# Current_Shunts.net
KiCad netlist of a schematic drawn in Altium Designer
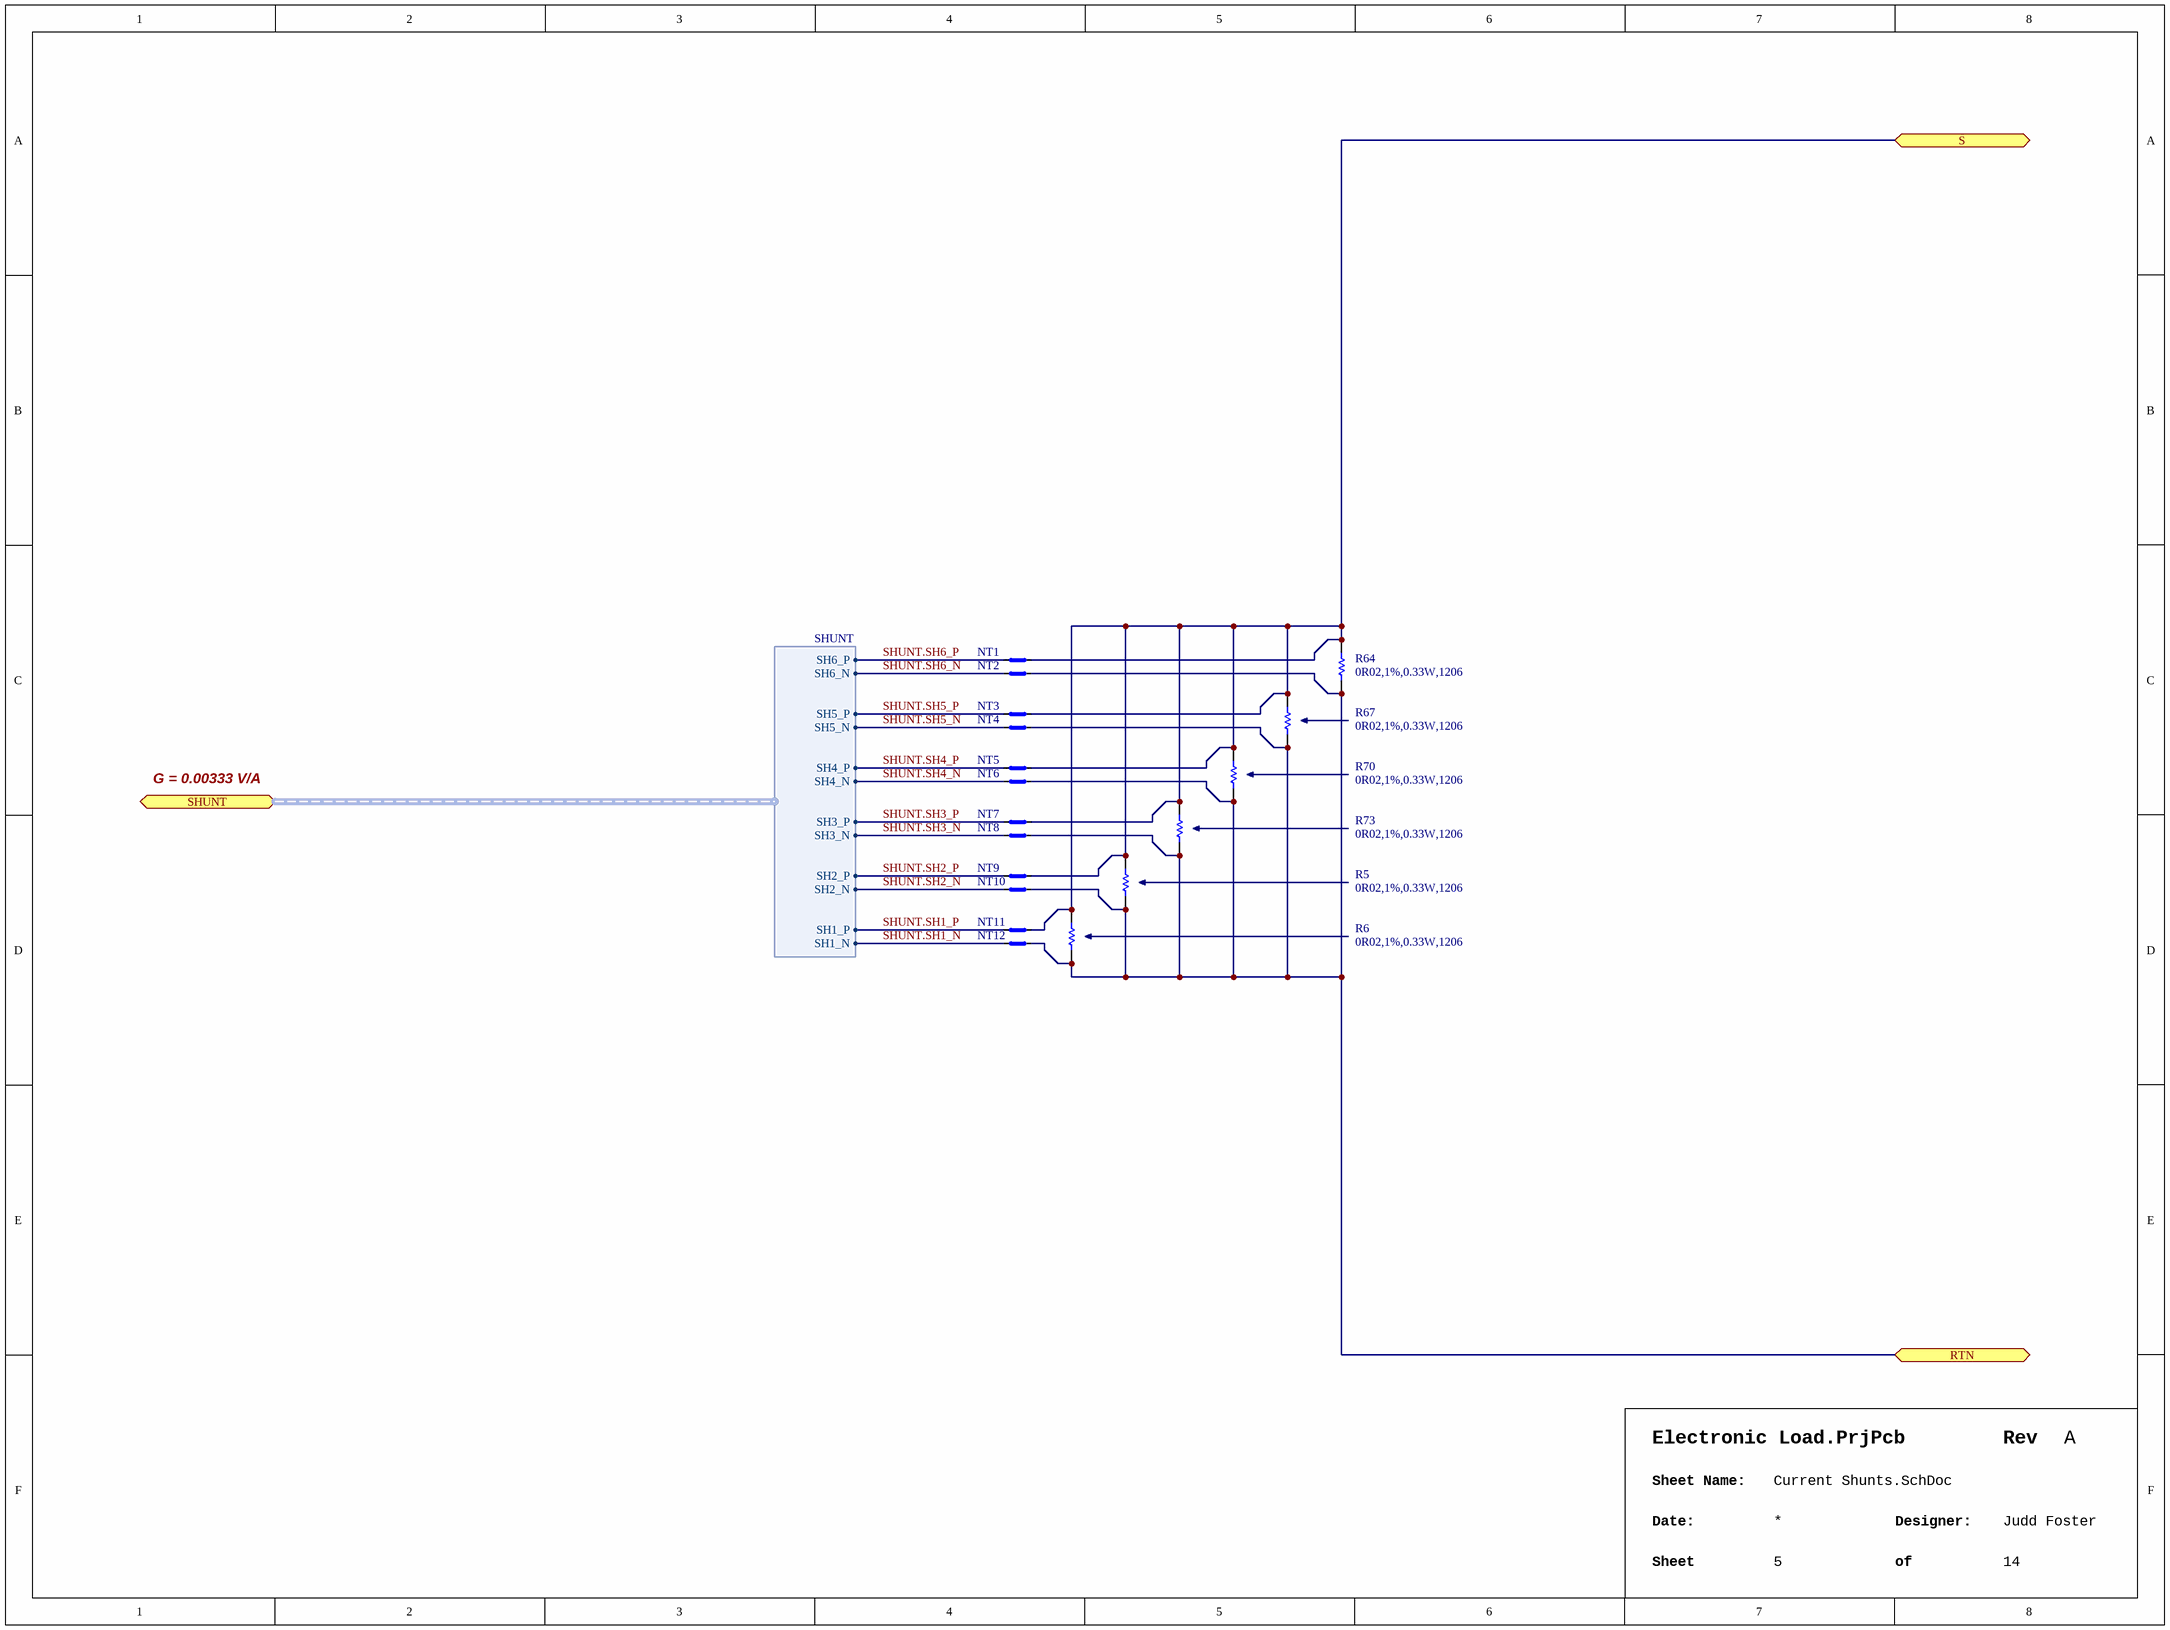
[diagram p0: Current Shunts.SchDoc]

(export (version "E")
  (design (tool "Eeschema 10.0.6"))
  (components
    (comp (ref "NT1")
      (value "NETTIE")
      (footprint "NETTIE_150X300UM")
      (description "Net Tie")
      (fields (field (name "CREATEDBY") "Judd Foster"))
      (libsource (lib "Component Library") (part "NETTIE"))
    )
    (comp (ref "NT2")
      (value "NETTIE")
      (footprint "NETTIE_150X300UM")
      (description "Net Tie")
      (fields (field (name "CREATEDBY") "Judd Foster"))
      (libsource (lib "Component Library") (part "NETTIE"))
    )
    (comp (ref "NT3")
      (value "NETTIE")
      (footprint "NETTIE_150X300UM")
      (description "Net Tie")
      (fields (field (name "CREATEDBY") "Judd Foster"))
      (libsource (lib "Component Library") (part "NETTIE"))
    )
    (comp (ref "NT4")
      (value "NETTIE")
      (footprint "NETTIE_150X300UM")
      (description "Net Tie")
      (fields (field (name "CREATEDBY") "Judd Foster"))
      (libsource (lib "Component Library") (part "NETTIE"))
    )
    (comp (ref "NT5")
      (value "NETTIE")
      (footprint "NETTIE_150X300UM")
      (description "Net Tie")
      (fields (field (name "CREATEDBY") "Judd Foster"))
      (libsource (lib "Component Library") (part "NETTIE"))
    )
    (comp (ref "NT6")
      (value "NETTIE")
      (footprint "NETTIE_150X300UM")
      (description "Net Tie")
      (fields (field (name "CREATEDBY") "Judd Foster"))
      (libsource (lib "Component Library") (part "NETTIE"))
    )
    (comp (ref "NT7")
      (value "NETTIE")
      (footprint "NETTIE_150X300UM")
      (description "Net Tie")
      (fields (field (name "CREATEDBY") "Judd Foster"))
      (libsource (lib "Component Library") (part "NETTIE"))
    )
    (comp (ref "NT8")
      (value "NETTIE")
      (footprint "NETTIE_150X300UM")
      (description "Net Tie")
      (fields (field (name "CREATEDBY") "Judd Foster"))
      (libsource (lib "Component Library") (part "NETTIE"))
    )
    (comp (ref "NT9")
      (value "NETTIE")
      (footprint "NETTIE_150X300UM")
      (description "Net Tie")
      (fields (field (name "CREATEDBY") "Judd Foster"))
      (libsource (lib "Component Library") (part "NETTIE"))
    )
    (comp (ref "NT10")
      (value "NETTIE")
      (footprint "NETTIE_150X300UM")
      (description "Net Tie")
      (fields (field (name "CREATEDBY") "Judd Foster"))
      (libsource (lib "Component Library") (part "NETTIE"))
    )
    (comp (ref "NT11")
      (value "NETTIE")
      (footprint "NETTIE_150X300UM")
      (description "Net Tie")
      (fields (field (name "CREATEDBY") "Judd Foster"))
      (libsource (lib "Component Library") (part "NETTIE"))
    )
    (comp (ref "NT12")
      (value "NETTIE")
      (footprint "NETTIE_150X300UM")
      (description "Net Tie")
      (fields (field (name "CREATEDBY") "Judd Foster"))
      (libsource (lib "Component Library") (part "NETTIE"))
    )
    (comp (ref "R5")
      (value "0R02,1%,0.33W,1206")
      (footprint "RESC3216X06N")
      (description "333mW 20mÎ© 200V Â±1000ppm/â„ƒ Thick Film Resistor Â±1% 1206 Chip Resistor - Surface Mount ROHS")
      (fields
        (field (name "MANUFACTURER 1 PART NUMBER") "1206W3F200MT5E")
        (field (name "VENDOR 1 PART NUMBER") "C2765435")
        (field (name "CREATEDBY") "Judd Foster")
      )
      (libsource (lib "Component Library") (part "RES"))
    )
    (comp (ref "R6")
      (value "0R02,1%,0.33W,1206")
      (footprint "RESC3216X06N")
      (description "333mW 20mÎ© 200V Â±1000ppm/â„ƒ Thick Film Resistor Â±1% 1206 Chip Resistor - Surface Mount ROHS")
      (fields
        (field (name "MANUFACTURER 1 PART NUMBER") "1206W3F200MT5E")
        (field (name "VENDOR 1 PART NUMBER") "C2765435")
        (field (name "CREATEDBY") "Judd Foster")
      )
      (libsource (lib "Component Library") (part "RES"))
    )
    (comp (ref "R64")
      (value "0R02,1%,0.33W,1206")
      (footprint "RESC3216X06N")
      (description "333mW 20mÎ© 200V Â±1000ppm/â„ƒ Thick Film Resistor Â±1% 1206 Chip Resistor - Surface Mount ROHS")
      (fields
        (field (name "MANUFACTURER 1 PART NUMBER") "1206W3F200MT5E")
        (field (name "VENDOR 1 PART NUMBER") "C2765435")
        (field (name "CREATEDBY") "Judd Foster")
      )
      (libsource (lib "Component Library") (part "RES"))
    )
    (comp (ref "R67")
      (value "0R02,1%,0.33W,1206")
      (footprint "RESC3216X06N")
      (description "333mW 20mÎ© 200V Â±1000ppm/â„ƒ Thick Film Resistor Â±1% 1206 Chip Resistor - Surface Mount ROHS")
      (fields
        (field (name "MANUFACTURER 1 PART NUMBER") "1206W3F200MT5E")
        (field (name "VENDOR 1 PART NUMBER") "C2765435")
        (field (name "CREATEDBY") "Judd Foster")
      )
      (libsource (lib "Component Library") (part "RES"))
    )
    (comp (ref "R70")
      (value "0R02,1%,0.33W,1206")
      (footprint "RESC3216X06N")
      (description "333mW 20mÎ© 200V Â±1000ppm/â„ƒ Thick Film Resistor Â±1% 1206 Chip Resistor - Surface Mount ROHS")
      (fields
        (field (name "MANUFACTURER 1 PART NUMBER") "1206W3F200MT5E")
        (field (name "VENDOR 1 PART NUMBER") "C2765435")
        (field (name "CREATEDBY") "Judd Foster")
      )
      (libsource (lib "Component Library") (part "RES"))
    )
    (comp (ref "R73")
      (value "0R02,1%,0.33W,1206")
      (footprint "RESC3216X06N")
      (description "333mW 20mÎ© 200V Â±1000ppm/â„ƒ Thick Film Resistor Â±1% 1206 Chip Resistor - Surface Mount ROHS")
      (fields
        (field (name "MANUFACTURER 1 PART NUMBER") "1206W3F200MT5E")
        (field (name "VENDOR 1 PART NUMBER") "C2765435")
        (field (name "CREATEDBY") "Judd Foster")
      )
      (libsource (lib "Component Library") (part "RES"))
    )
  )
  (nets
    (net (code "2") (name "/RTN") (class "Default")
      (node (ref "NT10") (pin "2") (pinfunction "2_2") (pintype "passive"))
      (node (ref "NT12") (pin "2") (pinfunction "2_2") (pintype "passive"))
      (node (ref "NT2") (pin "2") (pinfunction "2_2") (pintype "passive"))
      (node (ref "NT4") (pin "2") (pinfunction "2_2") (pintype "passive"))
      (node (ref "NT6") (pin "2") (pinfunction "2_2") (pintype "passive"))
      (node (ref "NT8") (pin "2") (pinfunction "2_2") (pintype "passive"))
      (node (ref "R5") (pin "1") (pinfunction "1_1") (pintype "passive"))
      (node (ref "R6") (pin "1") (pinfunction "1_1") (pintype "passive"))
      (node (ref "R64") (pin "1") (pinfunction "1_1") (pintype "passive"))
      (node (ref "R67") (pin "1") (pinfunction "1_1") (pintype "passive"))
      (node (ref "R70") (pin "1") (pinfunction "1_1") (pintype "passive"))
      (node (ref "R73") (pin "1") (pinfunction "1_1") (pintype "passive"))
    )
    (net (code "3") (name "/S") (class "Default")
      (node (ref "NT1") (pin "2") (pinfunction "2_2") (pintype "passive"))
      (node (ref "NT11") (pin "2") (pinfunction "2_2") (pintype "passive"))
      (node (ref "NT3") (pin "2") (pinfunction "2_2") (pintype "passive"))
      (node (ref "NT5") (pin "2") (pinfunction "2_2") (pintype "passive"))
      (node (ref "NT7") (pin "2") (pinfunction "2_2") (pintype "passive"))
      (node (ref "NT9") (pin "2") (pinfunction "2_2") (pintype "passive"))
      (node (ref "R5") (pin "2") (pinfunction "2_2") (pintype "passive"))
      (node (ref "R6") (pin "2") (pinfunction "2_2") (pintype "passive"))
      (node (ref "R64") (pin "2") (pinfunction "2_2") (pintype "passive"))
      (node (ref "R67") (pin "2") (pinfunction "2_2") (pintype "passive"))
      (node (ref "R70") (pin "2") (pinfunction "2_2") (pintype "passive"))
      (node (ref "R73") (pin "2") (pinfunction "2_2") (pintype "passive"))
    )
    (net (code "4") (name "/SHUNT.SH1_N") (class "Default")
      (node (ref "NT12") (pin "1") (pinfunction "1_1") (pintype "passive"))
    )
    (net (code "5") (name "/SHUNT.SH1_P") (class "Default")
      (node (ref "NT11") (pin "1") (pinfunction "1_1") (pintype "passive"))
    )
    (net (code "6") (name "/SHUNT.SH2_N") (class "Default")
      (node (ref "NT10") (pin "1") (pinfunction "1_1") (pintype "passive"))
    )
    (net (code "7") (name "/SHUNT.SH2_P") (class "Default")
      (node (ref "NT9") (pin "1") (pinfunction "1_1") (pintype "passive"))
    )
    (net (code "8") (name "/SHUNT.SH3_N") (class "Default")
      (node (ref "NT8") (pin "1") (pinfunction "1_1") (pintype "passive"))
    )
    (net (code "9") (name "/SHUNT.SH3_P") (class "Default")
      (node (ref "NT7") (pin "1") (pinfunction "1_1") (pintype "passive"))
    )
    (net (code "10") (name "/SHUNT.SH4_N") (class "Default")
      (node (ref "NT6") (pin "1") (pinfunction "1_1") (pintype "passive"))
    )
    (net (code "11") (name "/SHUNT.SH4_P") (class "Default")
      (node (ref "NT5") (pin "1") (pinfunction "1_1") (pintype "passive"))
    )
    (net (code "12") (name "/SHUNT.SH5_N") (class "Default")
      (node (ref "NT4") (pin "1") (pinfunction "1_1") (pintype "passive"))
    )
    (net (code "13") (name "/SHUNT.SH5_P") (class "Default")
      (node (ref "NT3") (pin "1") (pinfunction "1_1") (pintype "passive"))
    )
    (net (code "14") (name "/SHUNT.SH6_N") (class "Default")
      (node (ref "NT2") (pin "1") (pinfunction "1_1") (pintype "passive"))
    )
    (net (code "15") (name "/SHUNT.SH6_P") (class "Default")
      (node (ref "NT1") (pin "1") (pinfunction "1_1") (pintype "passive"))
    )
  )
)
